# TopLevelSchem.net
KiCad netlist of a schematic drawn in Altium Designer
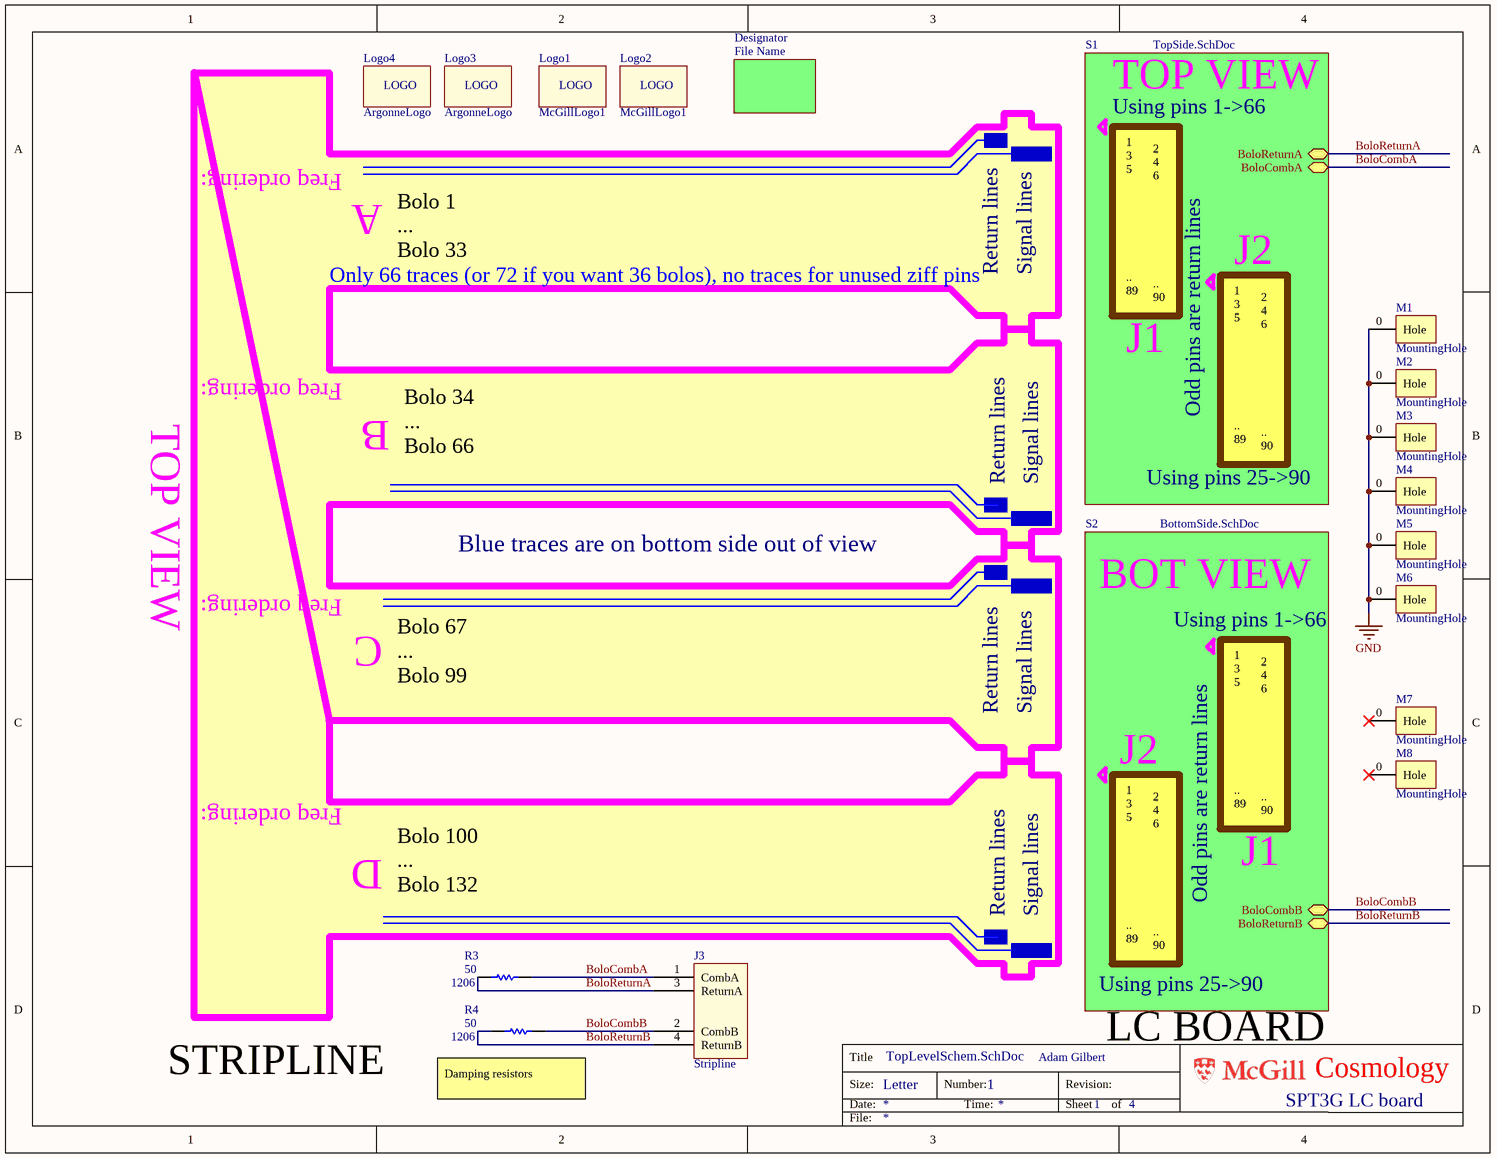
[diagram p0: TopLevelSchem.SchDoc]

(export (version "E")
  (design (tool "Eeschema 10.0.6"))
  (components
    (comp (ref "J3")
      (value "Stripline")
      (footprint "StriplineConnection")
      (libsource (lib "SPT3G_LCBoard") (part "Stripline4wire"))
    )
    (comp (ref "Logo1")
      (value "McGillLogo1")
      (footprint "McGillLogo1")
      (libsource (lib "SPT3G_LCBoard") (part "Logo"))
    )
    (comp (ref "Logo2")
      (value "McGillLogo1")
      (footprint "McGillLogo1")
      (libsource (lib "SPT3G_LCBoard") (part "Logo"))
    )
    (comp (ref "Logo3")
      (value "ArgonneLogo")
      (footprint "ArgonneLogo")
      (libsource (lib "SPT3G_AdapterBoard") (part "Logo"))
    )
    (comp (ref "Logo4")
      (value "ArgonneLogo")
      (footprint "ArgonneLogo")
      (libsource (lib "SPT3G_AdapterBoard") (part "Logo"))
    )
    (comp (ref "M1")
      (value "MountingHole")
      (footprint "MountingHole")
      (libsource (lib "SPT3G_LCBoard") (part "MountingHole"))
    )
    (comp (ref "M2")
      (value "MountingHole")
      (footprint "MountingHole")
      (libsource (lib "SPT3G_LCBoard") (part "MountingHole"))
    )
    (comp (ref "M3")
      (value "MountingHole")
      (footprint "MountingHole")
      (libsource (lib "SPT3G_LCBoard") (part "MountingHole"))
    )
    (comp (ref "M4")
      (value "MountingHole")
      (footprint "MountingHole")
      (libsource (lib "SPT3G_LCBoard") (part "MountingHole"))
    )
    (comp (ref "M5")
      (value "MountingHole")
      (footprint "MountingHole")
      (libsource (lib "SPT3G_LCBoard") (part "MountingHole"))
    )
    (comp (ref "M6")
      (value "MountingHole")
      (footprint "MountingHole")
      (libsource (lib "SPT3G_LCBoard") (part "MountingHole"))
    )
    (comp (ref "M7")
      (value "MountingHole")
      (footprint "MountingHole")
      (libsource (lib "SPT3G_LCBoard") (part "MountingHole"))
    )
    (comp (ref "M8")
      (value "MountingHole")
      (footprint "MountingHole")
      (libsource (lib "SPT3G_LCBoard") (part "MountingHole"))
    )
    (comp (ref "R3")
      (value "50")
      (footprint "1206")
      (description "Resistor")
      (libsource (lib "SPT3G_LCBoard") (part "Res1206"))
    )
    (comp (ref "R4")
      (value "50")
      (footprint "1206")
      (description "Resistor")
      (libsource (lib "SPT3G_LCBoard") (part "Res1206"))
    )
  )
  (nets
    (net (code "1") (name "/BoloCombA") (class "Default")
      (node (ref "J3") (pin "1") (pinfunction "CombA_1") (pintype "passive"))
      (node (ref "R3") (pin "1") (pinfunction "1_1") (pintype "passive"))
    )
    (net (code "2") (name "/BoloCombB") (class "Default")
      (node (ref "J3") (pin "2") (pinfunction "CombB_2") (pintype "passive"))
      (node (ref "R4") (pin "1") (pinfunction "1_1") (pintype "passive"))
    )
    (net (code "3") (name "/BoloReturnA") (class "Default")
      (node (ref "J3") (pin "3") (pinfunction "ReturnA_3") (pintype "passive"))
      (node (ref "R3") (pin "2") (pinfunction "2_2") (pintype "passive"))
    )
    (net (code "4") (name "/BoloReturnB") (class "Default")
      (node (ref "J3") (pin "4") (pinfunction "ReturnB_4") (pintype "passive"))
      (node (ref "R4") (pin "2") (pinfunction "2_2") (pintype "passive"))
    )
    (net (code "5") (name "GND") (class "Default")
      (node (ref "M1") (pin "0") (pinfunction "Hole_0") (pintype "passive"))
      (node (ref "M2") (pin "0") (pinfunction "Hole_0") (pintype "passive"))
      (node (ref "M3") (pin "0") (pinfunction "Hole_0") (pintype "passive"))
      (node (ref "M4") (pin "0") (pinfunction "Hole_0") (pintype "passive"))
      (node (ref "M5") (pin "0") (pinfunction "Hole_0") (pintype "passive"))
      (node (ref "M6") (pin "0") (pinfunction "Hole_0") (pintype "passive"))
    )
    (net (code "6") (name "unconnected-(M7-Hole-Pad0)") (class "Default")
      (node (ref "M7") (pin "0") (pinfunction "Hole_0") (pintype "passive+no_connect"))
    )
    (net (code "7") (name "unconnected-(M8-Hole-Pad0)") (class "Default")
      (node (ref "M8") (pin "0") (pinfunction "Hole_0") (pintype "passive+no_connect"))
    )
  )
)
